# STM32F303K8basic.net
KiCad netlist of a schematic drawn in EAGLE
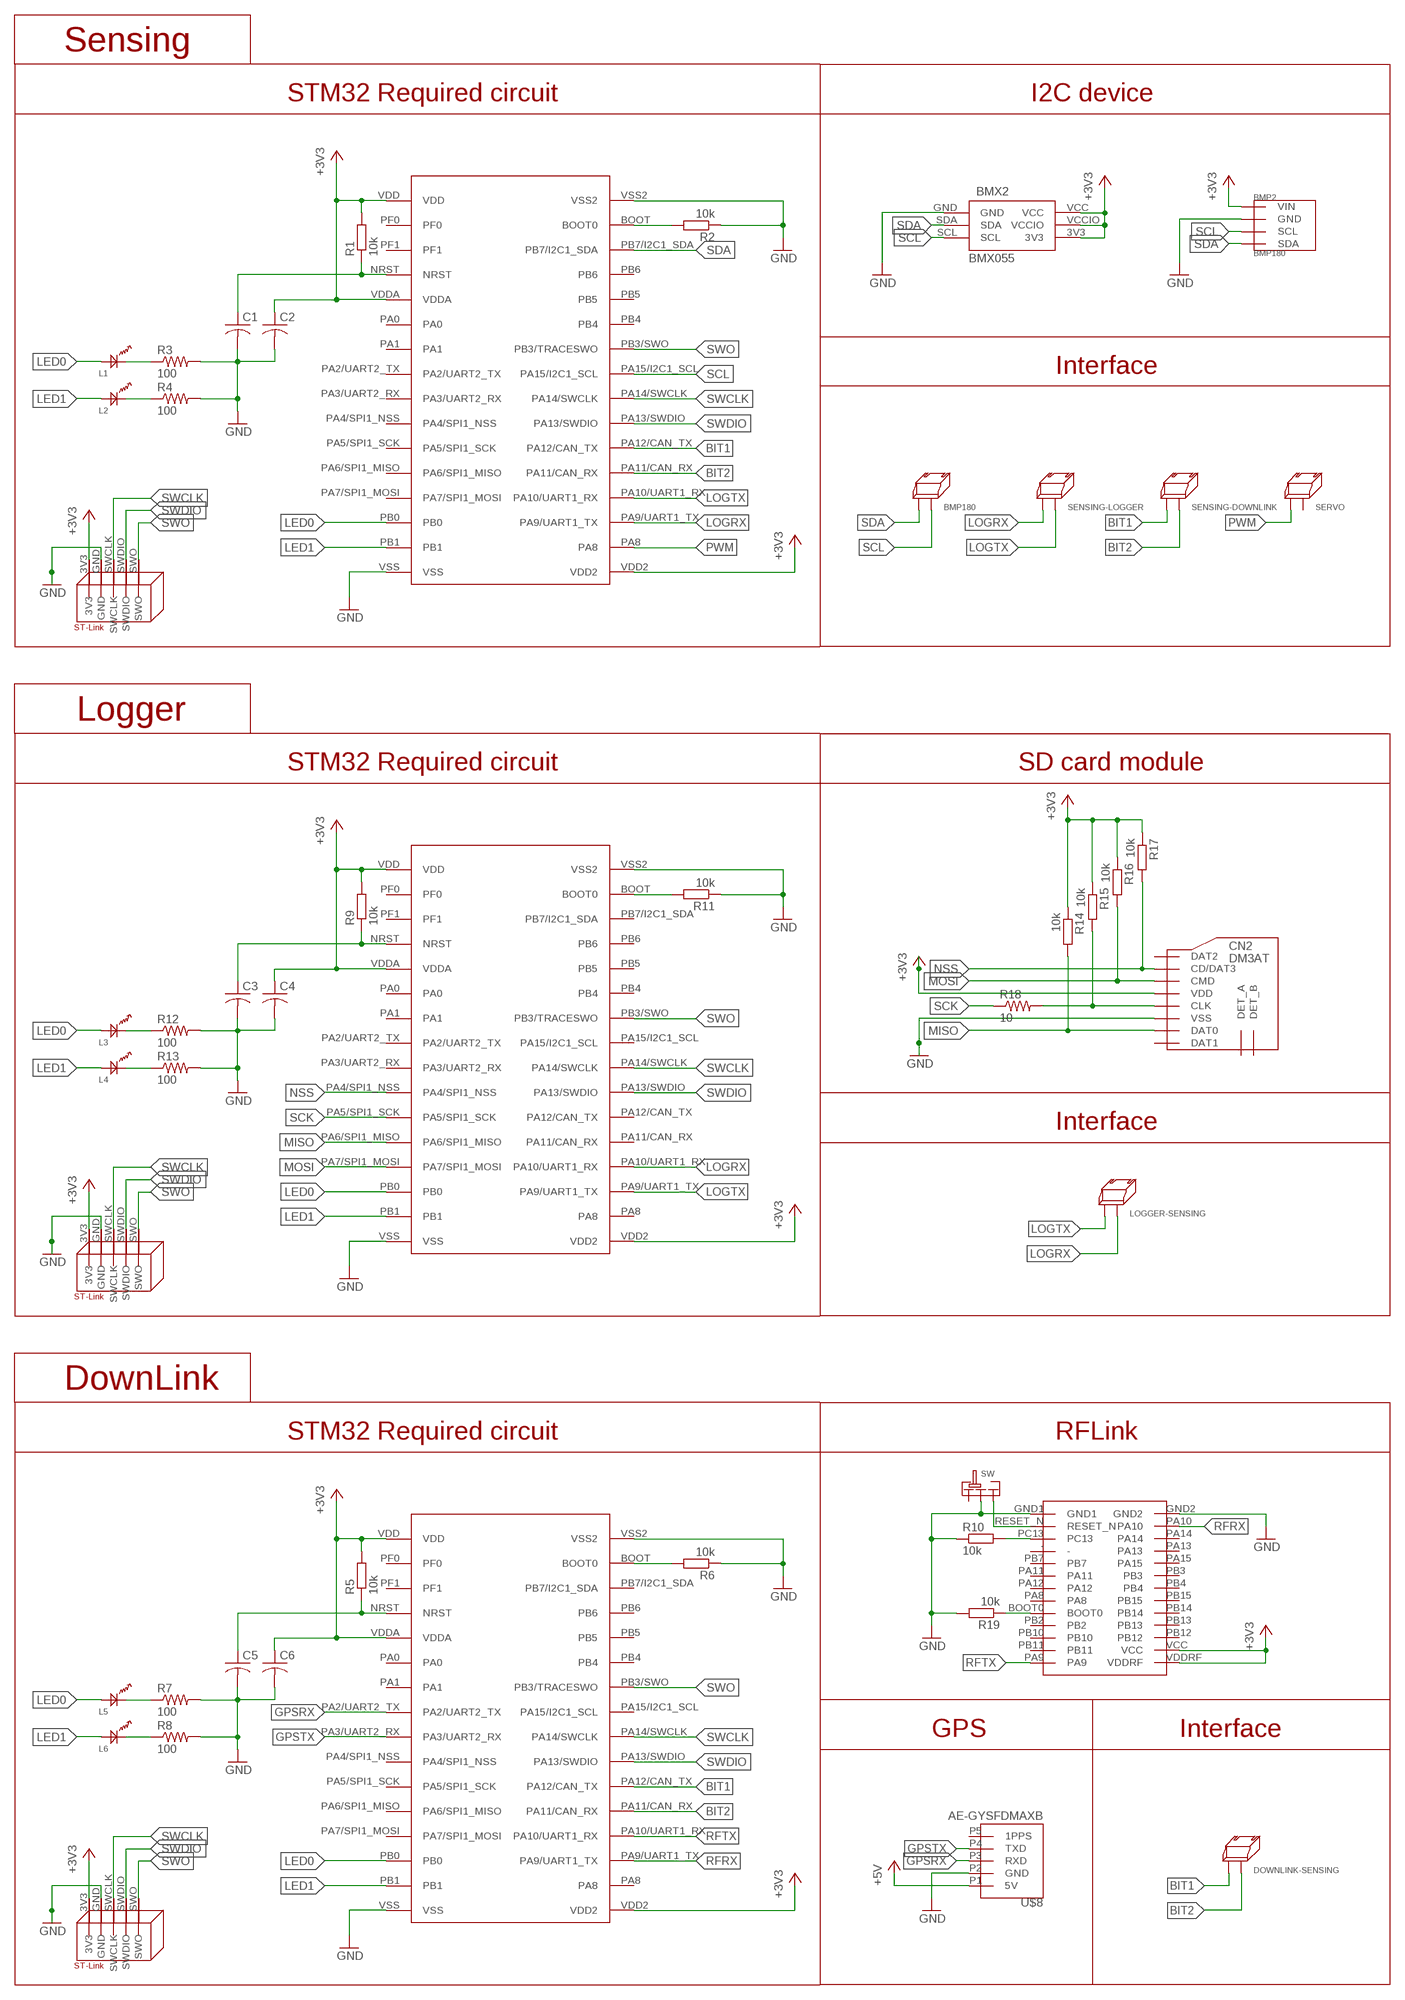
[diagram p0: schematic, sheet 1]

(export (version "E")
  (design (tool "Eeschema 10.0.6"))
  (components
    (comp (ref "BMP2")
      (value "BMP180")
      (footprint "eagle-import:GY-68")
      (libsource (lib "eagle-import") (part "BMP180"))
    )
    (comp (ref "BMP180")
      (value "2PIN_SIDE")
      (footprint "eagle-import:2PIN_SIDE")
      (libsource (lib "eagle-import") (part "2PIN_SIDE"))
    )
    (comp (ref "BMX2")
      (value "BMX055")
      (footprint "eagle-import:BMX055")
      (libsource (lib "eagle-import") (part "BMX055"))
    )
    (comp (ref "C1")
      (value "C-USC3216")
      (footprint "eagle-import:C3216")
      (libsource (lib "eagle-import") (part "C-USC3216"))
    )
    (comp (ref "C2")
      (value "C-USC3216")
      (footprint "eagle-import:C3216")
      (libsource (lib "eagle-import") (part "C-USC3216"))
    )
    (comp (ref "C3")
      (value "C-USC3216")
      (footprint "eagle-import:C3216")
      (libsource (lib "eagle-import") (part "C-USC3216"))
    )
    (comp (ref "C4")
      (value "C-USC3216")
      (footprint "eagle-import:C3216")
      (libsource (lib "eagle-import") (part "C-USC3216"))
    )
    (comp (ref "C5")
      (value "C-USC3216")
      (footprint "eagle-import:C3216")
      (libsource (lib "eagle-import") (part "C-USC3216"))
    )
    (comp (ref "C6")
      (value "C-USC3216")
      (footprint "eagle-import:C3216")
      (libsource (lib "eagle-import") (part "C-USC3216"))
    )
    (comp (ref "CN2")
      (value "DM3AT")
      (footprint "eagle-import:DM3AT")
      (libsource (lib "eagle-import") (part "DM3AT"))
    )
    (comp (ref "DOWNLINK-SENSING")
      (value "2PIN_SIDE")
      (footprint "eagle-import:2PIN_SIDE")
      (libsource (lib "eagle-import") (part "2PIN_SIDE"))
    )
    (comp (ref "L1")
      (value "OSXX1608C1A")
      (footprint "eagle-import:OSXX1608C1A")
      (libsource (lib "eagle-import") (part "OSXX1608C1A"))
    )
    (comp (ref "L2")
      (value "OSXX1608C1A")
      (footprint "eagle-import:OSXX1608C1A")
      (libsource (lib "eagle-import") (part "OSXX1608C1A"))
    )
    (comp (ref "L3")
      (value "OSXX1608C1A")
      (footprint "eagle-import:OSXX1608C1A")
      (libsource (lib "eagle-import") (part "OSXX1608C1A"))
    )
    (comp (ref "L4")
      (value "OSXX1608C1A")
      (footprint "eagle-import:OSXX1608C1A")
      (libsource (lib "eagle-import") (part "OSXX1608C1A"))
    )
    (comp (ref "L5")
      (value "OSXX1608C1A")
      (footprint "eagle-import:OSXX1608C1A")
      (libsource (lib "eagle-import") (part "OSXX1608C1A"))
    )
    (comp (ref "L6")
      (value "OSXX1608C1A")
      (footprint "eagle-import:OSXX1608C1A")
      (libsource (lib "eagle-import") (part "OSXX1608C1A"))
    )
    (comp (ref "LOGGER-SENSING")
      (value "2PIN_SIDE")
      (footprint "eagle-import:2PIN_SIDE")
      (libsource (lib "eagle-import") (part "2PIN_SIDE"))
    )
    (comp (ref "R1")
      (value "10k")
      (footprint "eagle-import:R0603")
      (libsource (lib "eagle-import") (part "R-EU_R0603"))
    )
    (comp (ref "R2")
      (value "10k")
      (footprint "eagle-import:R0603")
      (libsource (lib "eagle-import") (part "R-EU_R0603"))
    )
    (comp (ref "R3")
      (value "100")
      (footprint "eagle-import:R0603")
      (libsource (lib "eagle-import") (part "R-US_R0603"))
    )
    (comp (ref "R4")
      (value "100")
      (footprint "eagle-import:R0603")
      (libsource (lib "eagle-import") (part "R-US_R0603"))
    )
    (comp (ref "R5")
      (value "10k")
      (footprint "eagle-import:R0603")
      (libsource (lib "eagle-import") (part "R-EU_R0603"))
    )
    (comp (ref "R6")
      (value "10k")
      (footprint "eagle-import:R0603")
      (libsource (lib "eagle-import") (part "R-EU_R0603"))
    )
    (comp (ref "R7")
      (value "100")
      (footprint "eagle-import:R0603")
      (libsource (lib "eagle-import") (part "R-US_R0603"))
    )
    (comp (ref "R8")
      (value "100")
      (footprint "eagle-import:R0603")
      (libsource (lib "eagle-import") (part "R-US_R0603"))
    )
    (comp (ref "R9")
      (value "10k")
      (footprint "eagle-import:R0603")
      (libsource (lib "eagle-import") (part "R-EU_R0603"))
    )
    (comp (ref "R10")
      (value "10k")
      (footprint "eagle-import:R0603")
      (libsource (lib "eagle-import") (part "R-EU_R0603"))
    )
    (comp (ref "R11")
      (value "10k")
      (footprint "eagle-import:R0603")
      (libsource (lib "eagle-import") (part "R-EU_R0603"))
    )
    (comp (ref "R12")
      (value "100")
      (footprint "eagle-import:R0603")
      (libsource (lib "eagle-import") (part "R-US_R0603"))
    )
    (comp (ref "R13")
      (value "100")
      (footprint "eagle-import:R0603")
      (libsource (lib "eagle-import") (part "R-US_R0603"))
    )
    (comp (ref "R14")
      (value "10k")
      (footprint "eagle-import:R0603")
      (libsource (lib "eagle-import") (part "R-EU_R0603"))
    )
    (comp (ref "R15")
      (value "10k")
      (footprint "eagle-import:R0603")
      (libsource (lib "eagle-import") (part "R-EU_R0603"))
    )
    (comp (ref "R16")
      (value "10k")
      (footprint "eagle-import:R0603")
      (libsource (lib "eagle-import") (part "R-EU_R0603"))
    )
    (comp (ref "R17")
      (value "10k")
      (footprint "eagle-import:R0603")
      (libsource (lib "eagle-import") (part "R-EU_R0603"))
    )
    (comp (ref "R18")
      (value "10")
      (footprint "eagle-import:R2512")
      (libsource (lib "eagle-import") (part "R-US_R2512"))
    )
    (comp (ref "R19")
      (value "10k")
      (footprint "eagle-import:R0603")
      (libsource (lib "eagle-import") (part "R-EU_R0603"))
    )
    (comp (ref "SENSING-DOWNLINK")
      (value "2PIN_SIDE")
      (footprint "eagle-import:2PIN_SIDE")
      (libsource (lib "eagle-import") (part "2PIN_SIDE"))
    )
    (comp (ref "SENSING-LOGGER")
      (value "2PIN_SIDE")
      (footprint "eagle-import:2PIN_SIDE")
      (libsource (lib "eagle-import") (part "2PIN_SIDE"))
    )
    (comp (ref "SERVO")
      (value "2PIN_SIDE")
      (footprint "eagle-import:2PIN_SIDE")
      (libsource (lib "eagle-import") (part "2PIN_SIDE"))
    )
    (comp (ref "SW")
      (value "SRIDE_SWITCH")
      (footprint "eagle-import:SRIDE_SWITCH")
      (libsource (lib "eagle-import") (part "SRIDE_SWITCH"))
    )
    (comp (ref "U$1")
      (value "STM32F303K8")
      (footprint "eagle-import:STM32F303K8")
      (libsource (lib "eagle-import") (part "STM32F303K8"))
    )
    (comp (ref "U$2")
      (value "RM-92A")
      (footprint "eagle-import:RM-92A")
      (libsource (lib "eagle-import") (part "RM-92A"))
    )
    (comp (ref "U$3")
      (value "STLINK")
      (footprint "eagle-import:STLINK")
      (libsource (lib "eagle-import") (part "STLINK"))
    )
    (comp (ref "U$4")
      (value "STM32F303K8")
      (footprint "eagle-import:STM32F303K8")
      (libsource (lib "eagle-import") (part "STM32F303K8"))
    )
    (comp (ref "U$5")
      (value "STLINK")
      (footprint "eagle-import:STLINK")
      (libsource (lib "eagle-import") (part "STLINK"))
    )
    (comp (ref "U$6")
      (value "STM32F303K8")
      (footprint "eagle-import:STM32F303K8")
      (libsource (lib "eagle-import") (part "STM32F303K8"))
    )
    (comp (ref "U$7")
      (value "STLINK")
      (footprint "eagle-import:STLINK")
      (libsource (lib "eagle-import") (part "STLINK"))
    )
    (comp (ref "U$8")
      (value "AE-GYSFDMAXB")
      (footprint "eagle-import:AE-GYSFDMAXB")
      (libsource (lib "eagle-import") (part "AE-GYSFDMAXB"))
    )
  )
  (nets
    (net (code "1") (name "+3V3") (class "Default")
      (node (ref "BMP2") (pin "P1") (pinfunction "VIN_P1") (pintype "bidirectional"))
      (node (ref "BMX2") (pin "3V3") (pinfunction "3V3_3V3") (pintype "power_in"))
      (node (ref "BMX2") (pin "VCC") (pinfunction "VCC_VCC") (pintype "power_in"))
      (node (ref "BMX2") (pin "VCCIO") (pinfunction "VCCIO_VCCIO") (pintype "power_in"))
      (node (ref "C2") (pin "1") (pinfunction "1_1") (pintype "passive"))
      (node (ref "C4") (pin "1") (pinfunction "1_1") (pintype "passive"))
      (node (ref "C6") (pin "1") (pinfunction "1_1") (pintype "passive"))
      (node (ref "CN2") (pin "VDD") (pinfunction "VDD_VDD") (pintype "bidirectional"))
      (node (ref "R1") (pin "2") (pinfunction "2_2") (pintype "passive"))
      (node (ref "R14") (pin "1") (pinfunction "1_1") (pintype "passive"))
      (node (ref "R15") (pin "1") (pinfunction "1_1") (pintype "passive"))
      (node (ref "R16") (pin "1") (pinfunction "1_1") (pintype "passive"))
      (node (ref "R17") (pin "1") (pinfunction "1_1") (pintype "passive"))
      (node (ref "R5") (pin "2") (pinfunction "2_2") (pintype "passive"))
      (node (ref "R9") (pin "2") (pinfunction "2_2") (pintype "passive"))
      (node (ref "U$1") (pin "VDD") (pinfunction "VDD_VDD") (pintype "power_in"))
      (node (ref "U$1") (pin "VDD2") (pinfunction "VDD2_VDD2") (pintype "power_in"))
      (node (ref "U$1") (pin "VDDA") (pinfunction "VDDA_VDDA") (pintype "power_in"))
      (node (ref "U$2") (pin "VCC") (pinfunction "VCC_VCC") (pintype "bidirectional"))
      (node (ref "U$2") (pin "VDDRF") (pinfunction "VDDRF_VDDRF") (pintype "bidirectional"))
      (node (ref "U$3") (pin "3V3") (pinfunction "3V3_3V3") (pintype "bidirectional"))
      (node (ref "U$4") (pin "VDD") (pinfunction "VDD_VDD") (pintype "power_in"))
      (node (ref "U$4") (pin "VDD2") (pinfunction "VDD2_VDD2") (pintype "power_in"))
      (node (ref "U$4") (pin "VDDA") (pinfunction "VDDA_VDDA") (pintype "power_in"))
      (node (ref "U$5") (pin "3V3") (pinfunction "3V3_3V3") (pintype "bidirectional"))
      (node (ref "U$6") (pin "VDD") (pinfunction "VDD_VDD") (pintype "power_in"))
      (node (ref "U$6") (pin "VDD2") (pinfunction "VDD2_VDD2") (pintype "power_in"))
      (node (ref "U$6") (pin "VDDA") (pinfunction "VDDA_VDDA") (pintype "power_in"))
      (node (ref "U$7") (pin "3V3") (pinfunction "3V3_3V3") (pintype "bidirectional"))
    )
    (net (code "2") (name "+5V") (class "Default")
      (node (ref "U$8") (pin "P1") (pinfunction "5V_P1") (pintype "bidirectional"))
    )
    (net (code "3") (name "BIT1") (class "Default")
      (node (ref "DOWNLINK-SENSING") (pin "P$2") (pinfunction "P$2_P$2") (pintype "bidirectional"))
      (node (ref "SENSING-DOWNLINK") (pin "P$2") (pinfunction "P$2_P$2") (pintype "bidirectional"))
      (node (ref "U$1") (pin "PA12/CAN_TX") (pinfunction "PA12/CAN_TX_PA12/CAN_TX") (pintype "bidirectional"))
      (node (ref "U$6") (pin "PA12/CAN_TX") (pinfunction "PA12/CAN_TX_PA12/CAN_TX") (pintype "bidirectional"))
    )
    (net (code "4") (name "BIT2") (class "Default")
      (node (ref "DOWNLINK-SENSING") (pin "P$1") (pinfunction "P$1_P$1") (pintype "bidirectional"))
      (node (ref "SENSING-DOWNLINK") (pin "P$1") (pinfunction "P$1_P$1") (pintype "bidirectional"))
      (node (ref "U$1") (pin "PA11/CAN_RX") (pinfunction "PA11/CAN_RX_PA11/CAN_RX") (pintype "bidirectional"))
      (node (ref "U$6") (pin "PA11/CAN_RX") (pinfunction "PA11/CAN_RX_PA11/CAN_RX") (pintype "bidirectional"))
    )
    (net (code "5") (name "GND") (class "Default")
      (node (ref "BMP2") (pin "P2") (pinfunction "GND_P2") (pintype "bidirectional"))
      (node (ref "BMX2") (pin "GND") (pinfunction "GND_GND") (pintype "power_in"))
      (node (ref "C1") (pin "2") (pinfunction "2_2") (pintype "passive"))
      (node (ref "C2") (pin "2") (pinfunction "2_2") (pintype "passive"))
      (node (ref "C3") (pin "2") (pinfunction "2_2") (pintype "passive"))
      (node (ref "C4") (pin "2") (pinfunction "2_2") (pintype "passive"))
      (node (ref "C5") (pin "2") (pinfunction "2_2") (pintype "passive"))
      (node (ref "C6") (pin "2") (pinfunction "2_2") (pintype "passive"))
      (node (ref "CN2") (pin "VSS") (pinfunction "VSS_VSS") (pintype "bidirectional"))
      (node (ref "R10") (pin "1") (pinfunction "1_1") (pintype "passive"))
      (node (ref "R11") (pin "1") (pinfunction "1_1") (pintype "passive"))
      (node (ref "R12") (pin "2") (pinfunction "2_2") (pintype "passive"))
      (node (ref "R13") (pin "2") (pinfunction "2_2") (pintype "passive"))
      (node (ref "R19") (pin "2") (pinfunction "2_2") (pintype "passive"))
      (node (ref "R2") (pin "1") (pinfunction "1_1") (pintype "passive"))
      (node (ref "R3") (pin "2") (pinfunction "2_2") (pintype "passive"))
      (node (ref "R4") (pin "2") (pinfunction "2_2") (pintype "passive"))
      (node (ref "R6") (pin "1") (pinfunction "1_1") (pintype "passive"))
      (node (ref "R7") (pin "2") (pinfunction "2_2") (pintype "passive"))
      (node (ref "R8") (pin "2") (pinfunction "2_2") (pintype "passive"))
      (node (ref "SW") (pin "LR") (pinfunction "LR_LR") (pintype "bidirectional"))
      (node (ref "U$1") (pin "VSS") (pinfunction "VSS_VSS") (pintype "power_in"))
      (node (ref "U$1") (pin "VSS2") (pinfunction "VSS2_VSS2") (pintype "power_in"))
      (node (ref "U$2") (pin "GND1") (pinfunction "GND1_GND1") (pintype "bidirectional"))
      (node (ref "U$2") (pin "GND2") (pinfunction "GND2_GND2") (pintype "bidirectional"))
      (node (ref "U$3") (pin "GND") (pinfunction "GND_GND") (pintype "bidirectional"))
      (node (ref "U$4") (pin "VSS") (pinfunction "VSS_VSS") (pintype "power_in"))
      (node (ref "U$4") (pin "VSS2") (pinfunction "VSS2_VSS2") (pintype "power_in"))
      (node (ref "U$5") (pin "GND") (pinfunction "GND_GND") (pintype "bidirectional"))
      (node (ref "U$6") (pin "VSS") (pinfunction "VSS_VSS") (pintype "power_in"))
      (node (ref "U$6") (pin "VSS2") (pinfunction "VSS2_VSS2") (pintype "power_in"))
      (node (ref "U$7") (pin "GND") (pinfunction "GND_GND") (pintype "bidirectional"))
      (node (ref "U$8") (pin "P2") (pinfunction "GND_P2") (pintype "bidirectional"))
    )
    (net (code "6") (name "GPSRX") (class "Default")
      (node (ref "U$6") (pin "PA2/UART2_TX") (pinfunction "PA2/UART2_TX_PA2/UART2_TX") (pintype "bidirectional"))
      (node (ref "U$8") (pin "P3") (pinfunction "RXD_P3") (pintype "bidirectional"))
    )
    (net (code "7") (name "GPSTX") (class "Default")
      (node (ref "U$6") (pin "PA3/UART2_RX") (pinfunction "PA3/UART2_RX_PA3/UART2_RX") (pintype "bidirectional"))
      (node (ref "U$8") (pin "P4") (pinfunction "TXD_P4") (pintype "bidirectional"))
    )
    (net (code "8") (name "LED0") (class "Default")
      (node (ref "L1") (pin "AN") (pinfunction "AN_AN") (pintype "bidirectional"))
      (node (ref "L3") (pin "AN") (pinfunction "AN_AN") (pintype "bidirectional"))
      (node (ref "L5") (pin "AN") (pinfunction "AN_AN") (pintype "bidirectional"))
      (node (ref "U$1") (pin "PB0") (pinfunction "PB0_PB0") (pintype "bidirectional"))
      (node (ref "U$4") (pin "PB0") (pinfunction "PB0_PB0") (pintype "bidirectional"))
      (node (ref "U$6") (pin "PB0") (pinfunction "PB0_PB0") (pintype "bidirectional"))
    )
    (net (code "9") (name "LED1") (class "Default")
      (node (ref "L2") (pin "AN") (pinfunction "AN_AN") (pintype "bidirectional"))
      (node (ref "L4") (pin "AN") (pinfunction "AN_AN") (pintype "bidirectional"))
      (node (ref "L6") (pin "AN") (pinfunction "AN_AN") (pintype "bidirectional"))
      (node (ref "U$1") (pin "PB1") (pinfunction "PB1_PB1") (pintype "bidirectional"))
      (node (ref "U$4") (pin "PB1") (pinfunction "PB1_PB1") (pintype "bidirectional"))
      (node (ref "U$6") (pin "PB1") (pinfunction "PB1_PB1") (pintype "bidirectional"))
    )
    (net (code "10") (name "LOGRX") (class "Default")
      (node (ref "LOGGER-SENSING") (pin "P$1") (pinfunction "P$1_P$1") (pintype "bidirectional"))
      (node (ref "SENSING-LOGGER") (pin "P$2") (pinfunction "P$2_P$2") (pintype "bidirectional"))
      (node (ref "U$1") (pin "PA9/UART1_TX") (pinfunction "PA9/UART1_TX_PA9/UART1_TX") (pintype "bidirectional"))
      (node (ref "U$4") (pin "PA10/UART1_RX") (pinfunction "PA10/UART1_RX_PA10/UART1_RX") (pintype "bidirectional"))
    )
    (net (code "11") (name "LOGTX") (class "Default")
      (node (ref "LOGGER-SENSING") (pin "P$2") (pinfunction "P$2_P$2") (pintype "bidirectional"))
      (node (ref "SENSING-LOGGER") (pin "P$1") (pinfunction "P$1_P$1") (pintype "bidirectional"))
      (node (ref "U$1") (pin "PA10/UART1_RX") (pinfunction "PA10/UART1_RX_PA10/UART1_RX") (pintype "bidirectional"))
      (node (ref "U$4") (pin "PA9/UART1_TX") (pinfunction "PA9/UART1_TX_PA9/UART1_TX") (pintype "bidirectional"))
    )
    (net (code "12") (name "MISO") (class "Default")
      (node (ref "CN2") (pin "DAT0") (pinfunction "DAT0_DAT0") (pintype "bidirectional"))
      (node (ref "R14") (pin "2") (pinfunction "2_2") (pintype "passive"))
      (node (ref "U$4") (pin "PA6/SPI1_MISO") (pinfunction "PA6/SPI1_MISO_PA6/SPI1_MISO") (pintype "bidirectional"))
    )
    (net (code "13") (name "MOSI") (class "Default")
      (node (ref "CN2") (pin "CMD") (pinfunction "CMD_CMD") (pintype "bidirectional"))
      (node (ref "R16") (pin "2") (pinfunction "2_2") (pintype "passive"))
      (node (ref "U$4") (pin "PA7/SPI1_MOSI") (pinfunction "PA7/SPI1_MOSI_PA7/SPI1_MOSI") (pintype "bidirectional"))
    )
    (net (code "14") (name "NSS") (class "Default")
      (node (ref "CN2") (pin "CD/DAT3") (pinfunction "CD/DAT3_CD/DAT3") (pintype "bidirectional"))
      (node (ref "R17") (pin "2") (pinfunction "2_2") (pintype "passive"))
      (node (ref "U$4") (pin "PA4/SPI1_NSS") (pinfunction "PA4/SPI1_NSS_PA4/SPI1_NSS") (pintype "bidirectional"))
    )
    (net (code "15") (name "Net-(C1-Pad1)") (class "Default")
      (node (ref "C1") (pin "1") (pinfunction "1_1") (pintype "passive"))
      (node (ref "R1") (pin "1") (pinfunction "1_1") (pintype "passive"))
      (node (ref "U$1") (pin "NRST") (pinfunction "NRST_NRST") (pintype "bidirectional"))
    )
    (net (code "16") (name "Net-(C3-Pad1)") (class "Default")
      (node (ref "C3") (pin "1") (pinfunction "1_1") (pintype "passive"))
      (node (ref "R9") (pin "1") (pinfunction "1_1") (pintype "passive"))
      (node (ref "U$4") (pin "NRST") (pinfunction "NRST_NRST") (pintype "bidirectional"))
    )
    (net (code "17") (name "Net-(C5-Pad1)") (class "Default")
      (node (ref "C5") (pin "1") (pinfunction "1_1") (pintype "passive"))
      (node (ref "R5") (pin "1") (pinfunction "1_1") (pintype "passive"))
      (node (ref "U$6") (pin "NRST") (pinfunction "NRST_NRST") (pintype "bidirectional"))
    )
    (net (code "18") (name "Net-(L1-PadCT)") (class "Default")
      (node (ref "L1") (pin "CT") (pinfunction "CT_CT") (pintype "bidirectional"))
      (node (ref "R3") (pin "1") (pinfunction "1_1") (pintype "passive"))
    )
    (net (code "19") (name "Net-(L2-PadCT)") (class "Default")
      (node (ref "L2") (pin "CT") (pinfunction "CT_CT") (pintype "bidirectional"))
      (node (ref "R4") (pin "1") (pinfunction "1_1") (pintype "passive"))
    )
    (net (code "20") (name "Net-(L3-PadCT)") (class "Default")
      (node (ref "L3") (pin "CT") (pinfunction "CT_CT") (pintype "bidirectional"))
      (node (ref "R12") (pin "1") (pinfunction "1_1") (pintype "passive"))
    )
    (net (code "21") (name "Net-(L4-PadCT)") (class "Default")
      (node (ref "L4") (pin "CT") (pinfunction "CT_CT") (pintype "bidirectional"))
      (node (ref "R13") (pin "1") (pinfunction "1_1") (pintype "passive"))
    )
    (net (code "22") (name "Net-(L5-PadCT)") (class "Default")
      (node (ref "L5") (pin "CT") (pinfunction "CT_CT") (pintype "bidirectional"))
      (node (ref "R7") (pin "1") (pinfunction "1_1") (pintype "passive"))
    )
    (net (code "23") (name "Net-(L6-PadCT)") (class "Default")
      (node (ref "L6") (pin "CT") (pinfunction "CT_CT") (pintype "bidirectional"))
      (node (ref "R8") (pin "1") (pinfunction "1_1") (pintype "passive"))
    )
    (net (code "24") (name "Net-(R10-Pad2)") (class "Default")
      (node (ref "R10") (pin "2") (pinfunction "2_2") (pintype "passive"))
      (node (ref "U$2") (pin "PC13") (pinfunction "PC13_PC13") (pintype "bidirectional"))
    )
    (net (code "25") (name "Net-(R19-Pad1)") (class "Default")
      (node (ref "R19") (pin "1") (pinfunction "1_1") (pintype "passive"))
      (node (ref "U$2") (pin "BOOT0") (pinfunction "BOOT0_BOOT0") (pintype "bidirectional"))
    )
    (net (code "26") (name "Net-(SW-PadR)") (class "Default")
      (node (ref "SW") (pin "R") (pinfunction "R_R") (pintype "bidirectional"))
      (node (ref "U$2") (pin "RESET_N") (pinfunction "RESET_N_RESET_N") (pintype "bidirectional"))
    )
    (net (code "27") (name "Net-(U$1-BOOT0)") (class "Default")
      (node (ref "R2") (pin "2") (pinfunction "2_2") (pintype "passive"))
      (node (ref "U$1") (pin "BOOT") (pinfunction "BOOT0_BOOT") (pintype "bidirectional"))
    )
    (net (code "28") (name "Net-(U$4-BOOT0)") (class "Default")
      (node (ref "R11") (pin "2") (pinfunction "2_2") (pintype "passive"))
      (node (ref "U$4") (pin "BOOT") (pinfunction "BOOT0_BOOT") (pintype "bidirectional"))
    )
    (net (code "29") (name "Net-(U$6-BOOT0)") (class "Default")
      (node (ref "R6") (pin "2") (pinfunction "2_2") (pintype "passive"))
      (node (ref "U$6") (pin "BOOT") (pinfunction "BOOT0_BOOT") (pintype "bidirectional"))
    )
    (net (code "30") (name "PWM") (class "Default")
      (node (ref "SERVO") (pin "P$2") (pinfunction "P$2_P$2") (pintype "bidirectional"))
      (node (ref "U$1") (pin "PA8") (pinfunction "PA8_PA8") (pintype "bidirectional"))
    )
    (net (code "31") (name "RFRX") (class "Default")
      (node (ref "U$2") (pin "PA10") (pinfunction "PA10_PA10") (pintype "bidirectional"))
      (node (ref "U$6") (pin "PA9/UART1_TX") (pinfunction "PA9/UART1_TX_PA9/UART1_TX") (pintype "bidirectional"))
    )
    (net (code "32") (name "RFTX") (class "Default")
      (node (ref "U$2") (pin "PA9") (pinfunction "PA9_PA9") (pintype "bidirectional"))
      (node (ref "U$6") (pin "PA10/UART1_RX") (pinfunction "PA10/UART1_RX_PA10/UART1_RX") (pintype "bidirectional"))
    )
    (net (code "33") (name "SCK") (class "Default")
      (node (ref "CN2") (pin "CLK") (pinfunction "CLK_CLK") (pintype "bidirectional"))
      (node (ref "R15") (pin "2") (pinfunction "2_2") (pintype "passive"))
      (node (ref "R18") (pin "1") (pinfunction "1_1") (pintype "passive"))
      (node (ref "R18") (pin "2") (pinfunction "2_2") (pintype "passive"))
      (node (ref "U$4") (pin "PA5/SPI1_SCK") (pinfunction "PA5/SPI1_SCK_PA5/SPI1_SCK") (pintype "bidirectional"))
    )
    (net (code "34") (name "SCL") (class "Default")
      (node (ref "BMP180") (pin "P$1") (pinfunction "P$1_P$1") (pintype "bidirectional"))
      (node (ref "BMP2") (pin "P3") (pinfunction "SCL_P3") (pintype "bidirectional"))
      (node (ref "BMX2") (pin "SCL") (pinfunction "SCL_SCL") (pintype "bidirectional"))
      (node (ref "U$1") (pin "PA15/I2C1_SCL") (pinfunction "PA15/I2C1_SCL_PA15/I2C1_SCL") (pintype "bidirectional"))
    )
    (net (code "35") (name "SDA") (class "Default")
      (node (ref "BMP180") (pin "P$2") (pinfunction "P$2_P$2") (pintype "bidirectional"))
      (node (ref "BMP2") (pin "P4") (pinfunction "SDA_P4") (pintype "bidirectional"))
      (node (ref "BMX2") (pin "SDA") (pinfunction "SDA_SDA") (pintype "bidirectional"))
      (node (ref "U$1") (pin "PB7/I2C1_SDA") (pinfunction "PB7/I2C1_SDA_PB7/I2C1_SDA") (pintype "bidirectional"))
    )
    (net (code "36") (name "SWCLK") (class "Default")
      (node (ref "U$1") (pin "PA14/SWCLK") (pinfunction "PA14/SWCLK_PA14/SWCLK") (pintype "bidirectional"))
      (node (ref "U$3") (pin "SWCLK") (pinfunction "SWCLK_SWCLK") (pintype "bidirectional"))
      (node (ref "U$4") (pin "PA14/SWCLK") (pinfunction "PA14/SWCLK_PA14/SWCLK") (pintype "bidirectional"))
      (node (ref "U$5") (pin "SWCLK") (pinfunction "SWCLK_SWCLK") (pintype "bidirectional"))
      (node (ref "U$6") (pin "PA14/SWCLK") (pinfunction "PA14/SWCLK_PA14/SWCLK") (pintype "bidirectional"))
      (node (ref "U$7") (pin "SWCLK") (pinfunction "SWCLK_SWCLK") (pintype "bidirectional"))
    )
    (net (code "37") (name "SWDIO") (class "Default")
      (node (ref "U$1") (pin "PA13/SWDIO") (pinfunction "PA13/SWDIO_PA13/SWDIO") (pintype "bidirectional"))
      (node (ref "U$3") (pin "SWDIO") (pinfunction "SWDIO_SWDIO") (pintype "bidirectional"))
      (node (ref "U$4") (pin "PA13/SWDIO") (pinfunction "PA13/SWDIO_PA13/SWDIO") (pintype "bidirectional"))
      (node (ref "U$5") (pin "SWDIO") (pinfunction "SWDIO_SWDIO") (pintype "bidirectional"))
      (node (ref "U$6") (pin "PA13/SWDIO") (pinfunction "PA13/SWDIO_PA13/SWDIO") (pintype "bidirectional"))
      (node (ref "U$7") (pin "SWDIO") (pinfunction "SWDIO_SWDIO") (pintype "bidirectional"))
    )
    (net (code "38") (name "SWO") (class "Default")
      (node (ref "U$1") (pin "PB3/SWO") (pinfunction "PB3/TRACESWO_PB3/SWO") (pintype "bidirectional"))
      (node (ref "U$3") (pin "SWO") (pinfunction "SWO_SWO") (pintype "bidirectional"))
      (node (ref "U$4") (pin "PB3/SWO") (pinfunction "PB3/TRACESWO_PB3/SWO") (pintype "bidirectional"))
      (node (ref "U$5") (pin "SWO") (pinfunction "SWO_SWO") (pintype "bidirectional"))
      (node (ref "U$6") (pin "PB3/SWO") (pinfunction "PB3/TRACESWO_PB3/SWO") (pintype "bidirectional"))
      (node (ref "U$7") (pin "SWO") (pinfunction "SWO_SWO") (pintype "bidirectional"))
    )
    (net (code "39") (name "unconnected-(CN2-PadDAT1)") (class "Default")
      (node (ref "CN2") (pin "DAT1") (pinfunction "DAT1_DAT1") (pintype "bidirectional"))
    )
    (net (code "40") (name "unconnected-(CN2-PadDAT2)") (class "Default")
      (node (ref "CN2") (pin "DAT2") (pinfunction "DAT2_DAT2") (pintype "bidirectional"))
    )
    (net (code "41") (name "unconnected-(CN2-PadDET_A)") (class "Default")
      (node (ref "CN2") (pin "DET_A") (pinfunction "DET_A_DET_A") (pintype "bidirectional"))
    )
    (net (code "42") (name "unconnected-(CN2-PadDET_B)") (class "Default")
      (node (ref "CN2") (pin "DET_B") (pinfunction "DET_B_DET_B") (pintype "bidirectional"))
    )
    (net (code "43") (name "unconnected-(SERVO-PadP$1)") (class "Default")
      (node (ref "SERVO") (pin "P$1") (pinfunction "P$1_P$1") (pintype "bidirectional"))
    )
    (net (code "44") (name "unconnected-(SW-PadL)") (class "Default")
      (node (ref "SW") (pin "L") (pinfunction "L_L") (pintype "bidirectional"))
    )
    (net (code "45") (name "unconnected-(U$1-PadPA0)") (class "Default")
      (node (ref "U$1") (pin "PA0") (pinfunction "PA0_PA0") (pintype "bidirectional"))
    )
    (net (code "46") (name "unconnected-(U$1-PadPA1)") (class "Default")
      (node (ref "U$1") (pin "PA1") (pinfunction "PA1_PA1") (pintype "bidirectional"))
    )
    (net (code "47") (name "unconnected-(U$1-PadPA2{slash}UART2_TX)") (class "Default")
      (node (ref "U$1") (pin "PA2/UART2_TX") (pinfunction "PA2/UART2_TX_PA2/UART2_TX") (pintype "bidirectional"))
    )
    (net (code "48") (name "unconnected-(U$1-PadPA3{slash}UART2_RX)") (class "Default")
      (node (ref "U$1") (pin "PA3/UART2_RX") (pinfunction "PA3/UART2_RX_PA3/UART2_RX") (pintype "bidirectional"))
    )
    (net (code "49") (name "unconnected-(U$1-PadPA4{slash}SPI1_NSS)") (class "Default")
      (node (ref "U$1") (pin "PA4/SPI1_NSS") (pinfunction "PA4/SPI1_NSS_PA4/SPI1_NSS") (pintype "bidirectional"))
    )
    (net (code "50") (name "unconnected-(U$1-PadPA5{slash}SPI1_SCK)") (class "Default")
      (node (ref "U$1") (pin "PA5/SPI1_SCK") (pinfunction "PA5/SPI1_SCK_PA5/SPI1_SCK") (pintype "bidirectional"))
    )
    (net (code "51") (name "unconnected-(U$1-PadPA6{slash}SPI1_MISO)") (class "Default")
      (node (ref "U$1") (pin "PA6/SPI1_MISO") (pinfunction "PA6/SPI1_MISO_PA6/SPI1_MISO") (pintype "bidirectional"))
    )
    (net (code "52") (name "unconnected-(U$1-PadPA7{slash}SPI1_MOSI)") (class "Default")
      (node (ref "U$1") (pin "PA7/SPI1_MOSI") (pinfunction "PA7/SPI1_MOSI_PA7/SPI1_MOSI") (pintype "bidirectional"))
    )
    (net (code "53") (name "unconnected-(U$1-PadPB4)") (class "Default")
      (node (ref "U$1") (pin "PB4") (pinfunction "PB4_PB4") (pintype "bidirectional"))
    )
    (net (code "54") (name "unconnected-(U$1-PadPB5)") (class "Default")
      (node (ref "U$1") (pin "PB5") (pinfunction "PB5_PB5") (pintype "bidirectional"))
    )
    (net (code "55") (name "unconnected-(U$1-PadPB6)") (class "Default")
      (node (ref "U$1") (pin "PB6") (pinfunction "PB6_PB6") (pintype "bidirectional"))
    )
    (net (code "56") (name "unconnected-(U$1-PadPF0)") (class "Default")
      (node (ref "U$1") (pin "PF0") (pinfunction "PF0_PF0") (pintype "bidirectional"))
    )
    (net (code "57") (name "unconnected-(U$1-PadPF1)") (class "Default")
      (node (ref "U$1") (pin "PF1") (pinfunction "PF1_PF1") (pintype "bidirectional"))
    )
    (net (code "58") (name "unconnected-(U$2-Pad-)") (class "Default")
      (node (ref "U$2") (pin "-") (pinfunction "-_-") (pintype "bidirectional"))
    )
    (net (code "59") (name "unconnected-(U$2-PadPA8)") (class "Default")
      (node (ref "U$2") (pin "PA8") (pinfunction "PA8_PA8") (pintype "bidirectional"))
    )
    (net (code "60") (name "unconnected-(U$2-PadPA11)") (class "Default")
      (node (ref "U$2") (pin "PA11") (pinfunction "PA11_PA11") (pintype "bidirectional"))
    )
    (net (code "61") (name "unconnected-(U$2-PadPA12)") (class "Default")
      (node (ref "U$2") (pin "PA12") (pinfunction "PA12_PA12") (pintype "bidirectional"))
    )
    (net (code "62") (name "unconnected-(U$2-PadPA13)") (class "Default")
      (node (ref "U$2") (pin "PA13") (pinfunction "PA13_PA13") (pintype "bidirectional"))
    )
    (net (code "63") (name "unconnected-(U$2-PadPA14)") (class "Default")
      (node (ref "U$2") (pin "PA14") (pinfunction "PA14_PA14") (pintype "bidirectional"))
    )
    (net (code "64") (name "unconnected-(U$2-PadPA15)") (class "Default")
      (node (ref "U$2") (pin "PA15") (pinfunction "PA15_PA15") (pintype "bidirectional"))
    )
    (net (code "65") (name "unconnected-(U$2-PadPB2)") (class "Default")
      (node (ref "U$2") (pin "PB2") (pinfunction "PB2_PB2") (pintype "bidirectional"))
    )
    (net (code "66") (name "unconnected-(U$2-PadPB3)") (class "Default")
      (node (ref "U$2") (pin "PB3") (pinfunction "PB3_PB3") (pintype "bidirectional"))
    )
    (net (code "67") (name "unconnected-(U$2-PadPB4)") (class "Default")
      (node (ref "U$2") (pin "PB4") (pinfunction "PB4_PB4") (pintype "bidirectional"))
    )
    (net (code "68") (name "unconnected-(U$2-PadPB7)") (class "Default")
      (node (ref "U$2") (pin "PB7") (pinfunction "PB7_PB7") (pintype "bidirectional"))
    )
    (net (code "69") (name "unconnected-(U$2-PadPB10)") (class "Default")
      (node (ref "U$2") (pin "PB10") (pinfunction "PB10_PB10") (pintype "bidirectional"))
    )
    (net (code "70") (name "unconnected-(U$2-PadPB11)") (class "Default")
      (node (ref "U$2") (pin "PB11") (pinfunction "PB11_PB11") (pintype "bidirectional"))
    )
    (net (code "71") (name "unconnected-(U$2-PadPB12)") (class "Default")
      (node (ref "U$2") (pin "PB12") (pinfunction "PB12_PB12") (pintype "bidirectional"))
    )
    (net (code "72") (name "unconnected-(U$2-PadPB13)") (class "Default")
      (node (ref "U$2") (pin "PB13") (pinfunction "PB13_PB13") (pintype "bidirectional"))
    )
    (net (code "73") (name "unconnected-(U$2-PadPB14)") (class "Default")
      (node (ref "U$2") (pin "PB14") (pinfunction "PB14_PB14") (pintype "bidirectional"))
    )
    (net (code "74") (name "unconnected-(U$2-PadPB15)") (class "Default")
      (node (ref "U$2") (pin "PB15") (pinfunction "PB15_PB15") (pintype "bidirectional"))
    )
    (net (code "75") (name "unconnected-(U$4-PadPA0)") (class "Default")
      (node (ref "U$4") (pin "PA0") (pinfunction "PA0_PA0") (pintype "bidirectional"))
    )
    (net (code "76") (name "unconnected-(U$4-PadPA1)") (class "Default")
      (node (ref "U$4") (pin "PA1") (pinfunction "PA1_PA1") (pintype "bidirectional"))
    )
    (net (code "77") (name "unconnected-(U$4-PadPA2{slash}UART2_TX)") (class "Default")
      (node (ref "U$4") (pin "PA2/UART2_TX") (pinfunction "PA2/UART2_TX_PA2/UART2_TX") (pintype "bidirectional"))
    )
    (net (code "78") (name "unconnected-(U$4-PadPA3{slash}UART2_RX)") (class "Default")
      (node (ref "U$4") (pin "PA3/UART2_RX") (pinfunction "PA3/UART2_RX_PA3/UART2_RX") (pintype "bidirectional"))
    )
    (net (code "79") (name "unconnected-(U$4-PadPA8)") (class "Default")
      (node (ref "U$4") (pin "PA8") (pinfunction "PA8_PA8") (pintype "bidirectional"))
    )
    (net (code "80") (name "unconnected-(U$4-PadPA11{slash}CAN_RX)") (class "Default")
      (node (ref "U$4") (pin "PA11/CAN_RX") (pinfunction "PA11/CAN_RX_PA11/CAN_RX") (pintype "bidirectional"))
    )
    (net (code "81") (name "unconnected-(U$4-PadPA12{slash}CAN_TX)") (class "Default")
      (node (ref "U$4") (pin "PA12/CAN_TX") (pinfunction "PA12/CAN_TX_PA12/CAN_TX") (pintype "bidirectional"))
    )
    (net (code "82") (name "unconnected-(U$4-PadPA15{slash}I2C1_SCL)") (class "Default")
      (node (ref "U$4") (pin "PA15/I2C1_SCL") (pinfunction "PA15/I2C1_SCL_PA15/I2C1_SCL") (pintype "bidirectional"))
    )
    (net (code "83") (name "unconnected-(U$4-PadPB4)") (class "Default")
      (node (ref "U$4") (pin "PB4") (pinfunction "PB4_PB4") (pintype "bidirectional"))
    )
    (net (code "84") (name "unconnected-(U$4-PadPB5)") (class "Default")
      (node (ref "U$4") (pin "PB5") (pinfunction "PB5_PB5") (pintype "bidirectional"))
    )
    (net (code "85") (name "unconnected-(U$4-PadPB6)") (class "Default")
      (node (ref "U$4") (pin "PB6") (pinfunction "PB6_PB6") (pintype "bidirectional"))
    )
    (net (code "86") (name "unconnected-(U$4-PadPB7{slash}I2C1_SDA)") (class "Default")
      (node (ref "U$4") (pin "PB7/I2C1_SDA") (pinfunction "PB7/I2C1_SDA_PB7/I2C1_SDA") (pintype "bidirectional"))
    )
    (net (code "87") (name "unconnected-(U$4-PadPF0)") (class "Default")
      (node (ref "U$4") (pin "PF0") (pinfunction "PF0_PF0") (pintype "bidirectional"))
    )
    (net (code "88") (name "unconnected-(U$4-PadPF1)") (class "Default")
      (node (ref "U$4") (pin "PF1") (pinfunction "PF1_PF1") (pintype "bidirectional"))
    )
    (net (code "89") (name "unconnected-(U$6-PadPA0)") (class "Default")
      (node (ref "U$6") (pin "PA0") (pinfunction "PA0_PA0") (pintype "bidirectional"))
    )
    (net (code "90") (name "unconnected-(U$6-PadPA1)") (class "Default")
      (node (ref "U$6") (pin "PA1") (pinfunction "PA1_PA1") (pintype "bidirectional"))
    )
    (net (code "91") (name "unconnected-(U$6-PadPA4{slash}SPI1_NSS)") (class "Default")
      (node (ref "U$6") (pin "PA4/SPI1_NSS") (pinfunction "PA4/SPI1_NSS_PA4/SPI1_NSS") (pintype "bidirectional"))
    )
    (net (code "92") (name "unconnected-(U$6-PadPA5{slash}SPI1_SCK)") (class "Default")
      (node (ref "U$6") (pin "PA5/SPI1_SCK") (pinfunction "PA5/SPI1_SCK_PA5/SPI1_SCK") (pintype "bidirectional"))
    )
    (net (code "93") (name "unconnected-(U$6-PadPA6{slash}SPI1_MISO)") (class "Default")
      (node (ref "U$6") (pin "PA6/SPI1_MISO") (pinfunction "PA6/SPI1_MISO_PA6/SPI1_MISO") (pintype "bidirectional"))
    )
    (net (code "94") (name "unconnected-(U$6-PadPA7{slash}SPI1_MOSI)") (class "Default")
      (node (ref "U$6") (pin "PA7/SPI1_MOSI") (pinfunction "PA7/SPI1_MOSI_PA7/SPI1_MOSI") (pintype "bidirectional"))
    )
    (net (code "95") (name "unconnected-(U$6-PadPA8)") (class "Default")
      (node (ref "U$6") (pin "PA8") (pinfunction "PA8_PA8") (pintype "bidirectional"))
    )
    (net (code "96") (name "unconnected-(U$6-PadPA15{slash}I2C1_SCL)") (class "Default")
      (node (ref "U$6") (pin "PA15/I2C1_SCL") (pinfunction "PA15/I2C1_SCL_PA15/I2C1_SCL") (pintype "bidirectional"))
    )
    (net (code "97") (name "unconnected-(U$6-PadPB4)") (class "Default")
      (node (ref "U$6") (pin "PB4") (pinfunction "PB4_PB4") (pintype "bidirectional"))
    )
    (net (code "98") (name "unconnected-(U$6-PadPB5)") (class "Default")
      (node (ref "U$6") (pin "PB5") (pinfunction "PB5_PB5") (pintype "bidirectional"))
    )
    (net (code "99") (name "unconnected-(U$6-PadPB6)") (class "Default")
      (node (ref "U$6") (pin "PB6") (pinfunction "PB6_PB6") (pintype "bidirectional"))
    )
    (net (code "100") (name "unconnected-(U$6-PadPB7{slash}I2C1_SDA)") (class "Default")
      (node (ref "U$6") (pin "PB7/I2C1_SDA") (pinfunction "PB7/I2C1_SDA_PB7/I2C1_SDA") (pintype "bidirectional"))
    )
    (net (code "101") (name "unconnected-(U$6-PadPF0)") (class "Default")
      (node (ref "U$6") (pin "PF0") (pinfunction "PF0_PF0") (pintype "bidirectional"))
    )
    (net (code "102") (name "unconnected-(U$6-PadPF1)") (class "Default")
      (node (ref "U$6") (pin "PF1") (pinfunction "PF1_PF1") (pintype "bidirectional"))
    )
    (net (code "103") (name "unconnected-(U$8-1PPS-PadP5)") (class "Default")
      (node (ref "U$8") (pin "P5") (pinfunction "1PPS_P5") (pintype "bidirectional"))
    )
  )
)
